# IMX8_DISPLAY.net
KiCad netlist of a schematic drawn in Altium Designer
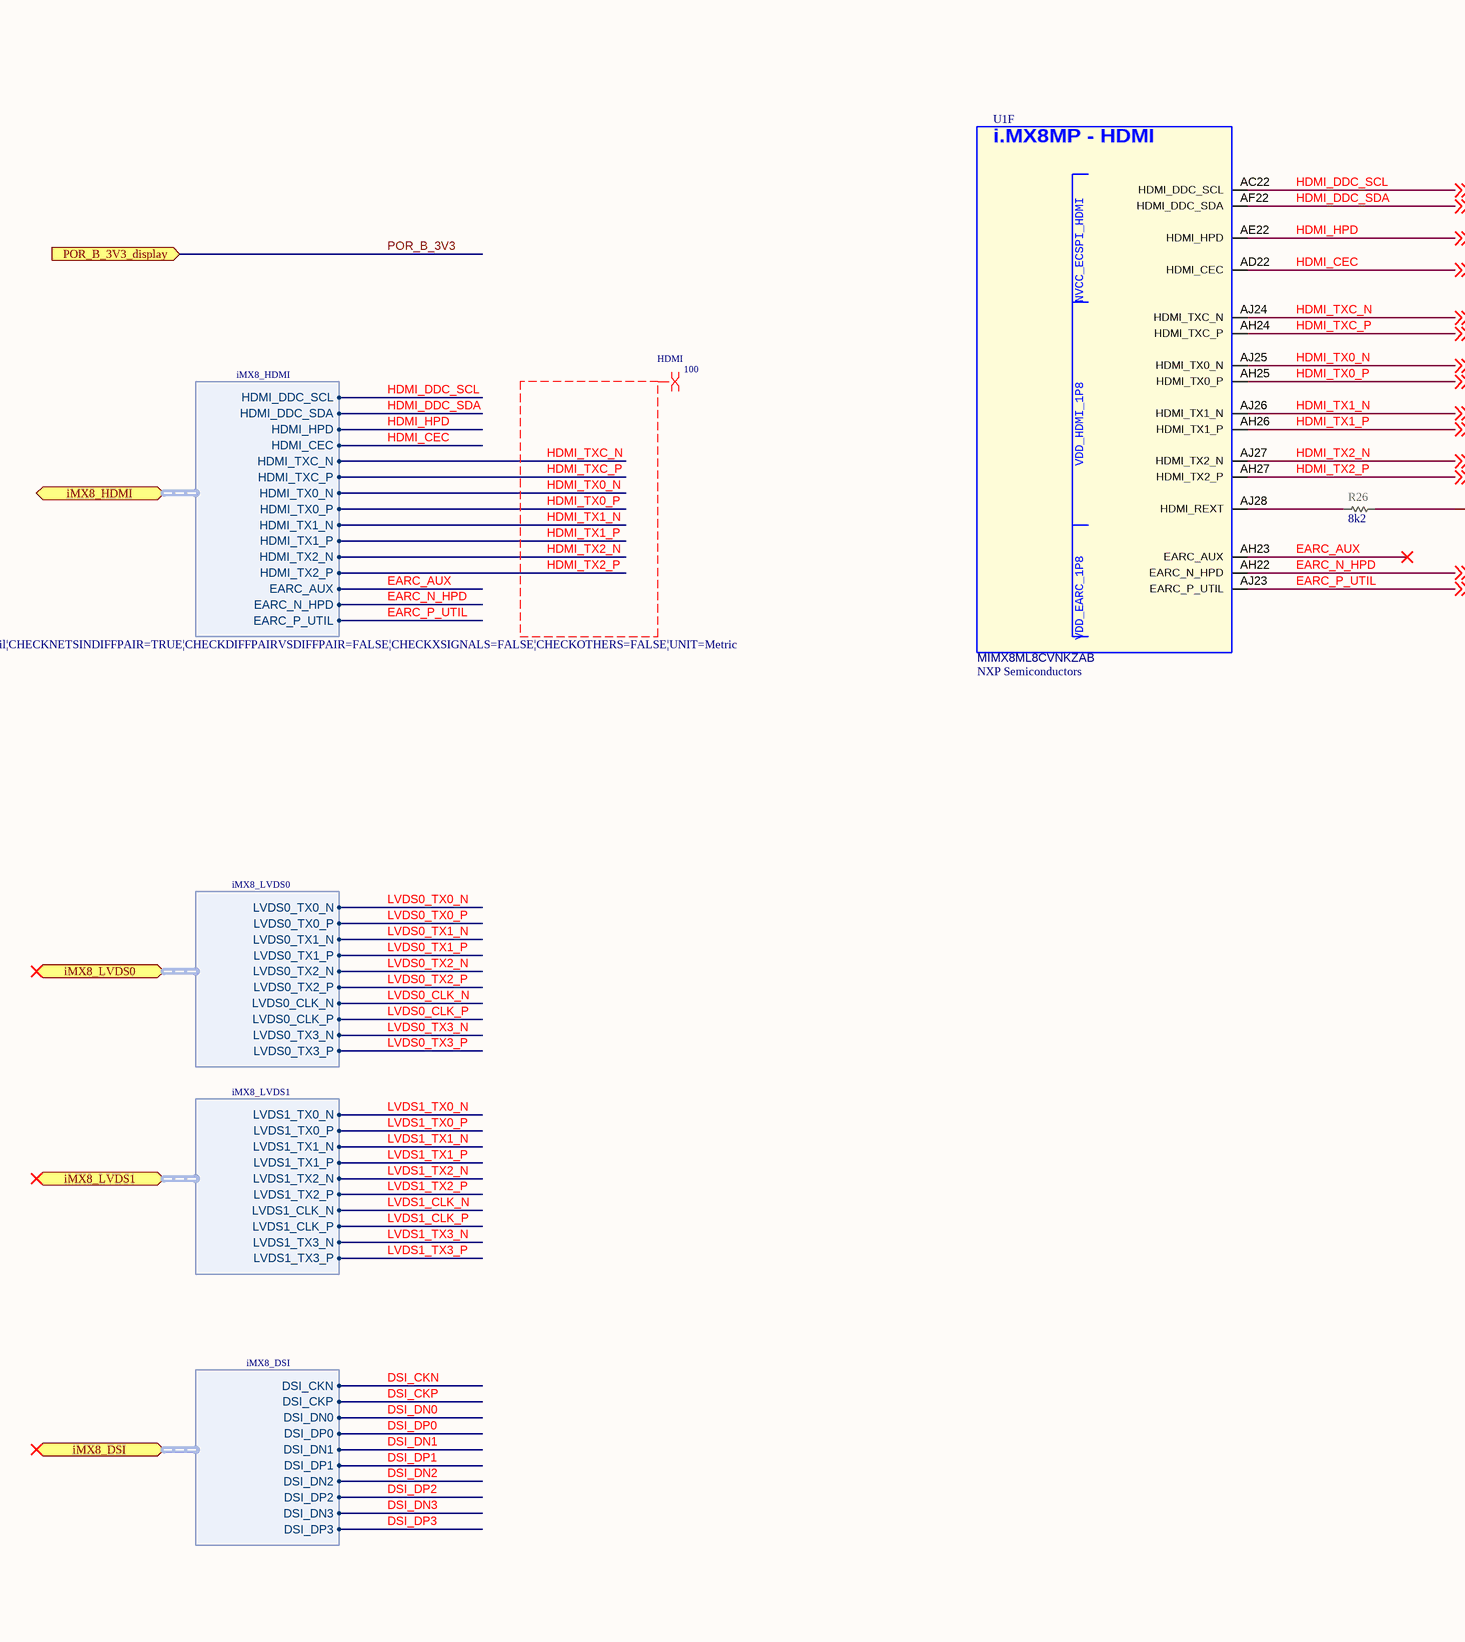
[diagram p0: IMX8_DISPLAY.SchDoc, left]
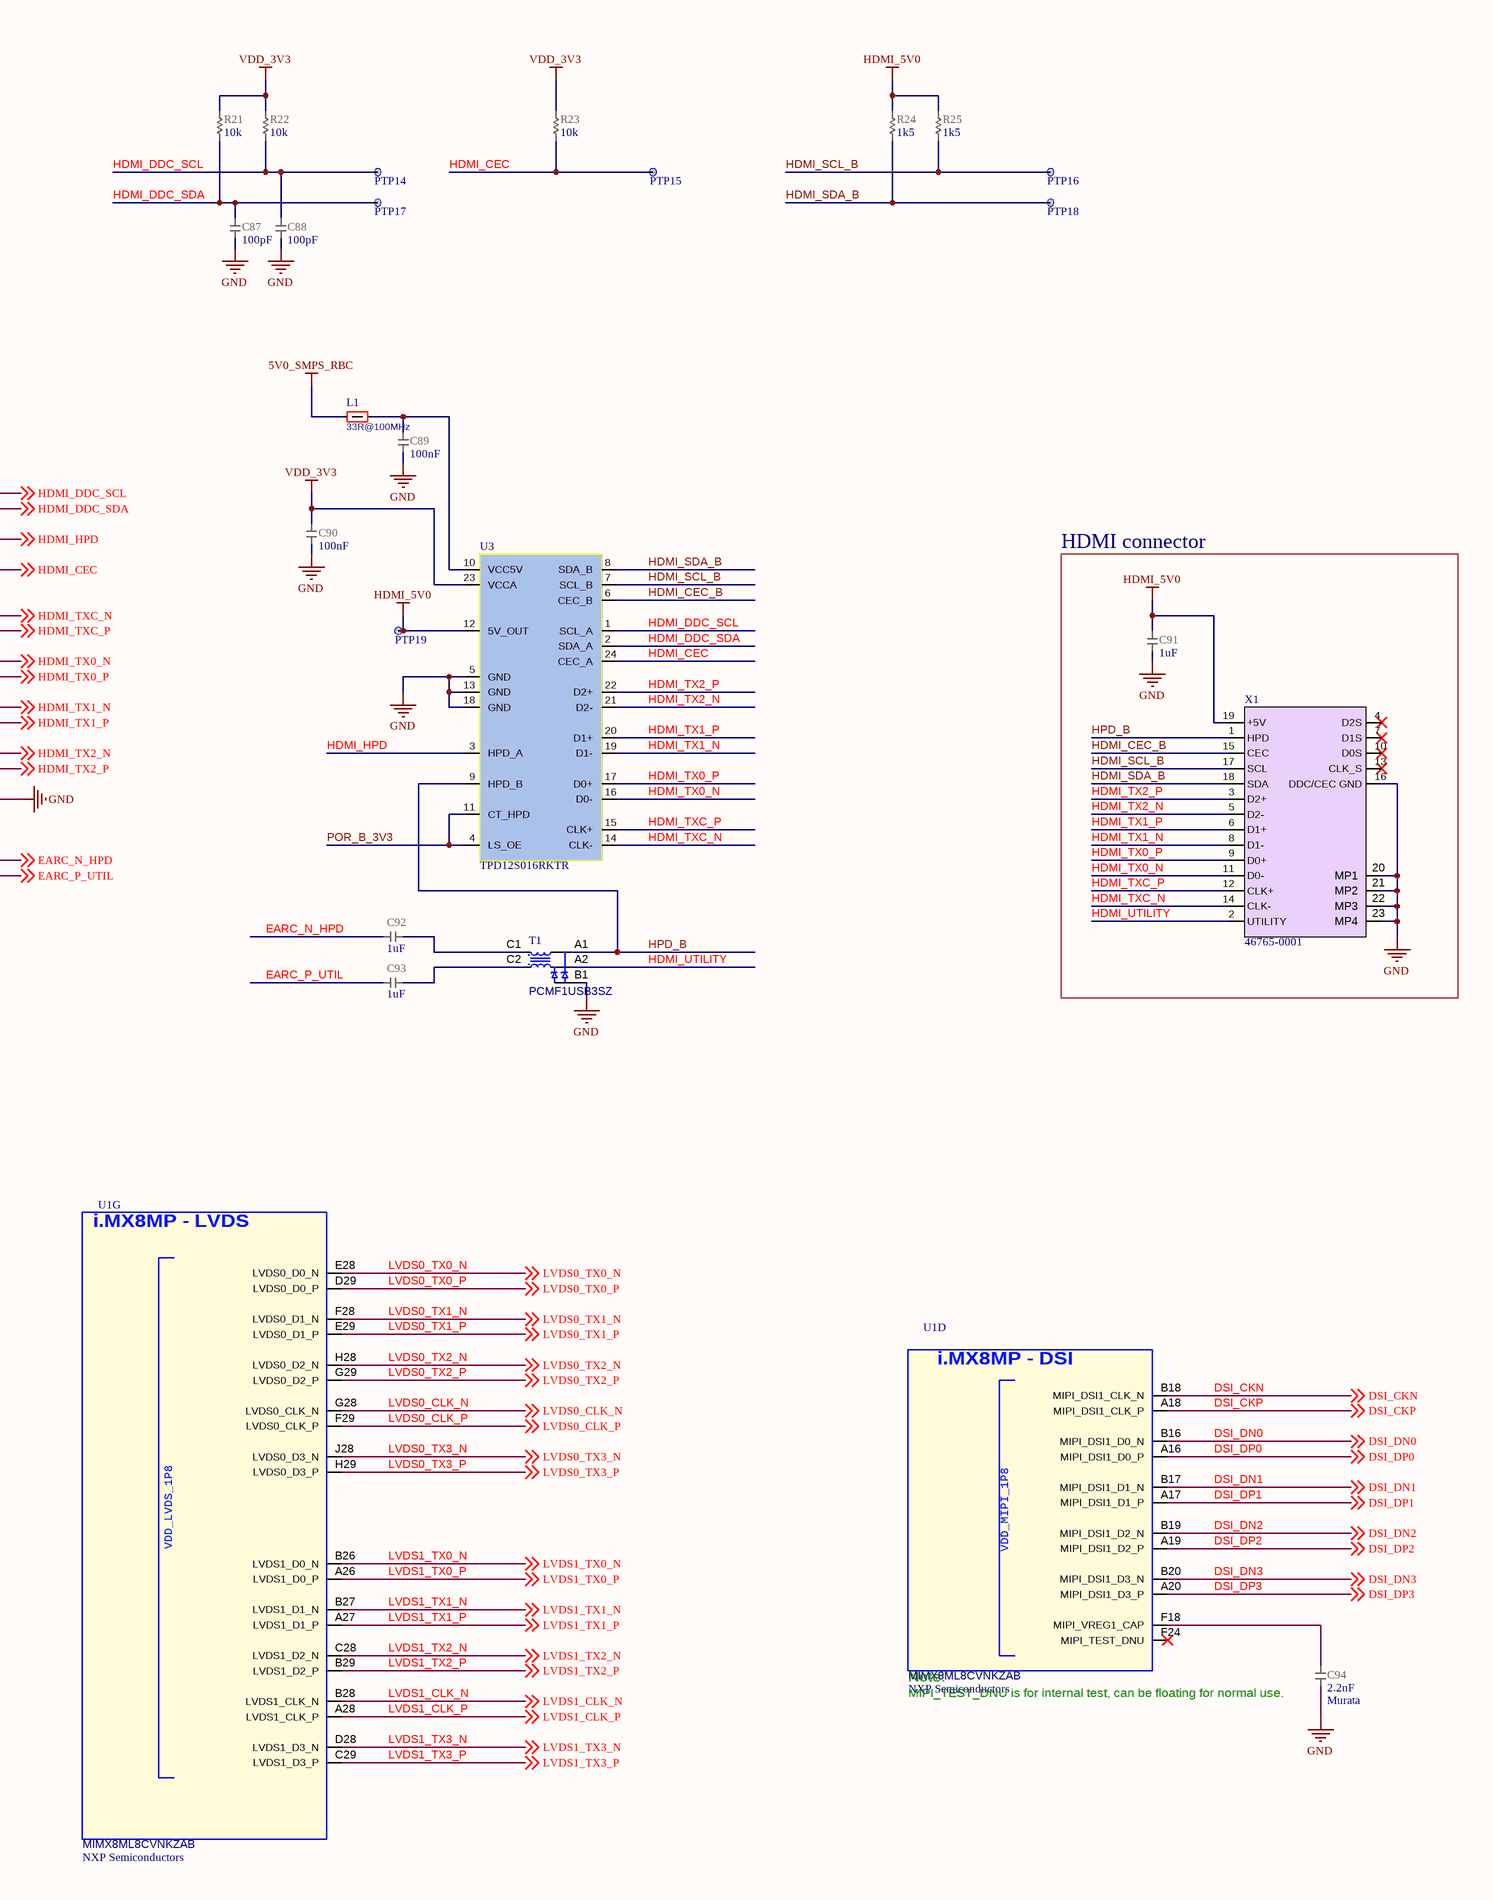
[diagram p1: IMX8_DISPLAY.SchDoc, right]

(export (version "E")
  (design (tool "Eeschema 10.0.6"))
  (components
    (comp (ref "C87")
      (value "100pF")
      (footprint "CAP_0201_UN1Q")
      (description "CAP")
      (fields (field (name "PART NUMBER") "CC0201KRX7R8BB101") (field (name "MANUFACTURER") "YAGEO"))
      (libsource (lib "TII_WS") (part "CAP_Common"))
    )
    (comp (ref "C88")
      (value "100pF")
      (footprint "CAP_0201_UN1Q")
      (description "CAP")
      (fields (field (name "PART NUMBER") "CC0201KRX7R8BB101") (field (name "MANUFACTURER") "YAGEO"))
      (libsource (lib "TII_WS") (part "CAP_Common"))
    )
    (comp (ref "C89")
      (value "100nF")
      (footprint "CAP_0201_UN1Q")
      (description "CAP")
      (fields (field (name "PART NUMBER") "GRM033C71C104KE14D") (field (name "MANUFACTURER") "Murata"))
      (libsource (lib "robo_cam") (part "CMP-001-000385-16"))
    )
    (comp (ref "C90")
      (value "100nF")
      (footprint "CAP_0201_UN1Q")
      (description "CAP")
      (fields (field (name "PART NUMBER") "GRM033C71C104KE14D") (field (name "MANUFACTURER") "Murata"))
      (libsource (lib "robo_cam") (part "CMP-001-000385-16"))
    )
    (comp (ref "C91")
      (value "1uF")
      (footprint "CAP_0201_UN1Q")
      (description "CAP")
      (fields (field (name "PART NUMBER") "KGM03CS61A105MH") (field (name "MANUFACTURER") "Kyocera"))
      (libsource (lib "robo_cam") (part "CMP-001-000336-15"))
    )
    (comp (ref "C92")
      (value "1uF")
      (footprint "CAP_0201_UN1Q")
      (description "CAP")
      (fields (field (name "PART NUMBER") "KGM03CS61A105MH") (field (name "MANUFACTURER") "Kyocera"))
      (libsource (lib "robo_cam") (part "CMP-001-000336-15"))
    )
    (comp (ref "C93")
      (value "1uF")
      (footprint "CAP_0201_UN1Q")
      (description "CAP")
      (fields (field (name "PART NUMBER") "KGM03CS61A105MH") (field (name "MANUFACTURER") "Kyocera"))
      (libsource (lib "robo_cam") (part "CMP-001-000336-15"))
    )
    (comp (ref "C94")
      (value "2.2nF")
      (footprint "CAP_0201_UN1Q")
      (description "CAP")
      (fields
        (field (name "PART NUMBER") "GRM033R71E222KA12J")
        (field (name "MANUFACTURER") "Murata")
        (field (name "MANUFACTURER_1") "Murata")
      )
      (libsource (lib "CM5_library") (part "CMP-001-000281-14"))
    )
    (comp (ref "L1")
      (value "33R@100MHz")
      (footprint "IND_0201_UN1Q")
      (description "FERRITE")
      (fields (field (name "MANUFACTURER") "Murata") (field (name "TOLERANCE") "25%"))
      (libsource (lib "robo_cam") (part "CMP-001-000744-7"))
    )
    (comp (ref "PTP14")
      (value "PTP_0.4mm")
      (footprint "PTP_0.4mm")
      (description "Production Testpoint 0.4mm. Flying probe. Use 1mm pitch.")
      (fields (field (name "PART NUMBER") "PTP 0.4mm"))
      (libsource (lib "robo_cam") (part "CMP-001-001296-3"))
    )
    (comp (ref "PTP15")
      (value "PTP_0.4mm")
      (footprint "PTP_0.4mm")
      (description "Production Testpoint 0.4mm. Flying probe. Use 1mm pitch.")
      (fields (field (name "PART NUMBER") "PTP 0.4mm"))
      (libsource (lib "robo_cam") (part "CMP-001-001296-3"))
    )
    (comp (ref "PTP16")
      (value "PTP_0.4mm")
      (footprint "PTP_0.4mm")
      (description "Production Testpoint 0.4mm. Flying probe. Use 1mm pitch.")
      (fields (field (name "PART NUMBER") "PTP 0.4mm"))
      (libsource (lib "robo_cam") (part "CMP-001-001296-3"))
    )
    (comp (ref "PTP17")
      (value "PTP_0.4mm")
      (footprint "PTP_0.4mm")
      (description "Production Testpoint 0.4mm. Flying probe. Use 1mm pitch.")
      (fields (field (name "PART NUMBER") "PTP 0.4mm"))
      (libsource (lib "robo_cam") (part "CMP-001-001296-3"))
    )
    (comp (ref "PTP18")
      (value "PTP_0.4mm")
      (footprint "PTP_0.4mm")
      (description "Production Testpoint 0.4mm. Flying probe. Use 1mm pitch.")
      (fields (field (name "PART NUMBER") "PTP 0.4mm"))
      (libsource (lib "robo_cam") (part "CMP-001-001296-3"))
    )
    (comp (ref "PTP19")
      (value "PTP_0.4mm")
      (footprint "PTP_0.4mm")
      (description "Production Testpoint 0.4mm. Flying probe. Use 1mm pitch.")
      (fields (field (name "PART NUMBER") "PTP 0.4mm"))
      (libsource (lib "robo_cam") (part "CMP-001-001296-3"))
    )
    (comp (ref "R21")
      (value "10k")
      (footprint "RES_0201_UN1Q")
      (description "RES")
      (fields (field (name "PART NUMBER") "RC0201FR-0710KL") (field (name "MANUFACTURER") "YAGEO"))
      (libsource (lib "robo_cam") (part "CMP-001-000446-13"))
    )
    (comp (ref "R22")
      (value "10k")
      (footprint "RES_0201_UN1Q")
      (description "RES")
      (fields (field (name "PART NUMBER") "RC0201FR-0710KL") (field (name "MANUFACTURER") "YAGEO"))
      (libsource (lib "robo_cam") (part "CMP-001-000446-13"))
    )
    (comp (ref "R23")
      (value "10k")
      (footprint "RES_0201_UN1Q")
      (description "RES")
      (fields (field (name "PART NUMBER") "RC0201FR-0710KL") (field (name "MANUFACTURER") "YAGEO"))
      (libsource (lib "robo_cam") (part "CMP-001-000446-13"))
    )
    (comp (ref "R24")
      (value "1k5")
      (footprint "RES_0201_UN1Q")
      (description "RES")
      (fields (field (name "PART NUMBER") "RC0201FR-071K5L") (field (name "MANUFACTURER") "YAGEO"))
      (libsource (lib "robo_cam") (part "CMP-001-000455-11"))
    )
    (comp (ref "R25")
      (value "1k5")
      (footprint "RES_0201_UN1Q")
      (description "RES")
      (fields (field (name "PART NUMBER") "RC0201FR-071K5L") (field (name "MANUFACTURER") "YAGEO"))
      (libsource (lib "robo_cam") (part "CMP-001-000455-11"))
    )
    (comp (ref "R26")
      (value "8k2")
      (footprint "RES_0201_UN1Q")
      (description "RES")
      (fields (field (name "TOLERANCE") "1%") (field (name "PART NUMBER") "ERJ1GNF8201C"))
      (libsource (lib "robo_cam") (part "CMP-001-001255-9"))
    )
    (comp (ref "T1")
      (value "EMI_ESD_PCMF1USB3SZ")
      (footprint "PCMF1USB3S_EMI")
      (description "EMI Filter with ESD 15kV differential pair")
      (fields
        (field (name "MANUFACTURER") "Nexperia")
        (field (name "PART NUMBER") "PCMF1USB3SZ")
        (field (name "MANUFACTURER PART NUMBER") "PCMF1USB3SZ")
        (field (name "SOURCE") "UUDET_KOMPONENTIT.SchLib")
      )
      (libsource (lib "robo_cam") (part "CMP-001-000967-4"))
    )
    (comp (ref "U1")
      (value "MIMX8ML8CVNKZAB")
      (footprint "BGA548C50P29X29_1500X1500X148")
      (description "CPU QUAD CORTEX A53+M4 1.6GHZ BGA548 Industrial")
      (fields
        (field (name "MANUFACTURER") "NXP SEMICONDUCTORS")
        (field (name "PART NUMBER") "MIMX8ML8CVNKZAB")
        (field (name "MANUFACTURER_1") "NXP Semiconductors")
        (field (name "SOURCE") "UUDET_KOMPONENTIT.SchLib")
      )
      (libsource (lib "robo_cam") (part "CMP-001-000983-8"))
    )
    (comp (ref "U3")
      (value "TPD12S016RKT")
      (footprint "UQFN24_RKT0024A_TI")
      (description "HDMI ESD Protection and I2C Level Shifting Buffer")
      (fields
        (field (name "MANUFACTURER") "Texas Instruments")
        (field (name "PART NUMBER") "TPD12S016RKTR")
        (field (name "MANUFACTURER PART NUMBER") "TPD12S016RKTR")
        (field (name "SOURCE") "UUDET_KOMPONENTIT.SchLib")
      )
      (libsource (lib "robo_cam") (part "CMP-031-000038-2"))
    )
    (comp (ref "X1")
      (value "Molex_uHDMI_46765-0001")
      (footprint "uHDMI-SMD-Molex")
      (description "Micro-HDMI connector, surface mount")
      (fields
        (field (name "MANUFACTURER") "Molex")
        (field (name "PART NUMBER") "46765-0001")
        (field (name "MANUFACTURER PART NUMBER") "46765-0001")
      )
      (libsource (lib "robo_cam") (part "CMP-001-000218-15"))
    )
  )
  (nets
    (net (code "5") (name "/EARC_AUX") (class "Default")
      (node (ref "U1") (pin "AH23") (pinfunction "EARC_AUX_AH23") (pintype "passive+no_connect"))
    )
    (net (code "6") (name "/HDMI_CEC_B") (class "Default")
      (node (ref "U3") (pin "6") (pinfunction "CEC_B_6") (pintype "passive"))
      (node (ref "X1") (pin "15") (pinfunction "CEC_15") (pintype "passive"))
    )
    (net (code "7") (name "/HDMI_SCL_B") (class "Default")
      (node (ref "PTP16") (pin "1") (pinfunction "TP_1") (pintype "passive"))
      (node (ref "R25") (pin "1") (pinfunction "1_1") (pintype "passive"))
      (node (ref "U3") (pin "7") (pinfunction "SCL_B_7") (pintype "passive"))
      (node (ref "X1") (pin "17") (pinfunction "SCL_17") (pintype "passive"))
    )
    (net (code "8") (name "/HDMI_SDA_B") (class "Default")
      (node (ref "PTP18") (pin "1") (pinfunction "TP_1") (pintype "passive"))
      (node (ref "R24") (pin "1") (pinfunction "1_1") (pintype "passive"))
      (node (ref "U3") (pin "8") (pinfunction "SDA_B_8") (pintype "passive"))
      (node (ref "X1") (pin "18") (pinfunction "SDA_18") (pintype "passive"))
    )
    (net (code "9") (name "/HDMI_UTILITY") (class "Default")
      (node (ref "T1") (pin "A2") (pinfunction "A2_A2") (pintype "passive"))
      (node (ref "X1") (pin "2") (pinfunction "UTILITY_2") (pintype "passive"))
    )
    (net (code "10") (name "/HPD_B") (class "Default")
      (node (ref "T1") (pin "A1") (pinfunction "A1_A1") (pintype "passive"))
      (node (ref "U3") (pin "9") (pinfunction "HPD_B_9") (pintype "passive"))
      (node (ref "X1") (pin "1") (pinfunction "HPD_1") (pintype "passive"))
    )
    (net (code "11") (name "/POR_B_3V3") (class "Default")
      (node (ref "U3") (pin "11") (pinfunction "CT_HPD_11") (pintype "passive"))
      (node (ref "U3") (pin "4") (pinfunction "LS_OE_4") (pintype "passive"))
    )
    (net (code "16") (name "5V0_SMPS_RBC") (class "Default")
      (node (ref "L1") (pin "1") (pinfunction "1_1") (pintype "passive"))
    )
    (net (code "17") (name "DSI_CKN") (class "Default")
      (node (ref "U1") (pin "B18") (pinfunction "MIPI_DSI1_CLK_N_B18") (pintype "passive"))
    )
    (net (code "18") (name "DSI_CKP") (class "Default")
      (node (ref "U1") (pin "A18") (pinfunction "MIPI_DSI1_CLK_P_A18") (pintype "passive"))
    )
    (net (code "19") (name "DSI_DN0") (class "Default")
      (node (ref "U1") (pin "B16") (pinfunction "MIPI_DSI1_D0_N_B16") (pintype "passive"))
    )
    (net (code "20") (name "DSI_DN1") (class "Default")
      (node (ref "U1") (pin "B17") (pinfunction "MIPI_DSI1_D1_N_B17") (pintype "passive"))
    )
    (net (code "21") (name "DSI_DN2") (class "Default")
      (node (ref "U1") (pin "B19") (pinfunction "MIPI_DSI1_D2_N_B19") (pintype "passive"))
    )
    (net (code "22") (name "DSI_DN3") (class "Default")
      (node (ref "U1") (pin "B20") (pinfunction "MIPI_DSI1_D3_N_B20") (pintype "passive"))
    )
    (net (code "23") (name "DSI_DP0") (class "Default")
      (node (ref "U1") (pin "A16") (pinfunction "MIPI_DSI1_D0_P_A16") (pintype "passive"))
    )
    (net (code "24") (name "DSI_DP1") (class "Default")
      (node (ref "U1") (pin "A17") (pinfunction "MIPI_DSI1_D1_P_A17") (pintype "passive"))
    )
    (net (code "25") (name "DSI_DP2") (class "Default")
      (node (ref "U1") (pin "A19") (pinfunction "MIPI_DSI1_D2_P_A19") (pintype "passive"))
    )
    (net (code "26") (name "DSI_DP3") (class "Default")
      (node (ref "U1") (pin "A20") (pinfunction "MIPI_DSI1_D3_P_A20") (pintype "passive"))
    )
    (net (code "27") (name "EARC_N_HPD") (class "Default")
      (node (ref "C92") (pin "1") (pinfunction "1_1") (pintype "passive"))
      (node (ref "U1") (pin "AH22") (pinfunction "EARC_N_HPD_AH22") (pintype "passive"))
    )
    (net (code "28") (name "EARC_P_UTIL") (class "Default")
      (node (ref "C93") (pin "1") (pinfunction "1_1") (pintype "passive"))
      (node (ref "U1") (pin "AJ23") (pinfunction "EARC_P_UTIL_AJ23") (pintype "passive"))
    )
    (net (code "29") (name "GND") (class "Default")
      (node (ref "C87") (pin "1") (pinfunction "1_1") (pintype "passive"))
      (node (ref "C88") (pin "1") (pinfunction "1_1") (pintype "passive"))
      (node (ref "C89") (pin "2") (pinfunction "2_2") (pintype "passive"))
      (node (ref "C90") (pin "2") (pinfunction "2_2") (pintype "passive"))
      (node (ref "C91") (pin "1") (pinfunction "1_1") (pintype "passive"))
      (node (ref "C94") (pin "1") (pinfunction "1_1") (pintype "passive"))
      (node (ref "R26") (pin "2") (pinfunction "2_2") (pintype "passive"))
      (node (ref "T1") (pin "B1") (pinfunction "B1_B1") (pintype "passive"))
      (node (ref "U3") (pin "13") (pinfunction "GND_13") (pintype "passive"))
      (node (ref "U3") (pin "18") (pinfunction "GND_18") (pintype "passive"))
      (node (ref "U3") (pin "5") (pinfunction "GND_5") (pintype "passive"))
      (node (ref "X1") (pin "16") (pinfunction "DDC/CEC_GND_16") (pintype "passive"))
      (node (ref "X1") (pin "20") (pinfunction "MP1_20") (pintype "passive"))
      (node (ref "X1") (pin "21") (pinfunction "MP2_21") (pintype "passive"))
      (node (ref "X1") (pin "22") (pinfunction "MP3_22") (pintype "passive"))
      (node (ref "X1") (pin "23") (pinfunction "MP4_23") (pintype "passive"))
    )
    (net (code "30") (name "HDMI_5V0") (class "Default")
      (node (ref "C91") (pin "2") (pinfunction "2_2") (pintype "passive"))
      (node (ref "PTP19") (pin "1") (pinfunction "TP_1") (pintype "passive"))
      (node (ref "R24") (pin "2") (pinfunction "2_2") (pintype "passive"))
      (node (ref "R25") (pin "2") (pinfunction "2_2") (pintype "passive"))
      (node (ref "U3") (pin "12") (pinfunction "5V_OUT_12") (pintype "passive"))
      (node (ref "X1") (pin "19") (pinfunction "+5V_19") (pintype "passive"))
    )
    (net (code "31") (name "HDMI_CEC") (class "Default")
      (node (ref "PTP15") (pin "1") (pinfunction "TP_1") (pintype "passive"))
      (node (ref "R23") (pin "1") (pinfunction "1_1") (pintype "passive"))
      (node (ref "U1") (pin "AD22") (pinfunction "HDMI_CEC_AD22") (pintype "passive"))
      (node (ref "U3") (pin "24") (pinfunction "CEC_A_24") (pintype "passive"))
    )
    (net (code "32") (name "HDMI_DDC_SCL") (class "Default")
      (node (ref "C88") (pin "2") (pinfunction "2_2") (pintype "passive"))
      (node (ref "PTP14") (pin "1") (pinfunction "TP_1") (pintype "passive"))
      (node (ref "R22") (pin "1") (pinfunction "1_1") (pintype "passive"))
      (node (ref "U1") (pin "AC22") (pinfunction "HDMI_DDC_SCL_AC22") (pintype "passive"))
      (node (ref "U3") (pin "1") (pinfunction "SCL_A_1") (pintype "passive"))
    )
    (net (code "33") (name "HDMI_DDC_SDA") (class "Default")
      (node (ref "C87") (pin "2") (pinfunction "2_2") (pintype "passive"))
      (node (ref "PTP17") (pin "1") (pinfunction "TP_1") (pintype "passive"))
      (node (ref "R21") (pin "1") (pinfunction "1_1") (pintype "passive"))
      (node (ref "U1") (pin "AF22") (pinfunction "HDMI_DDC_SDA_AF22") (pintype "passive"))
      (node (ref "U3") (pin "2") (pinfunction "SDA_A_2") (pintype "passive"))
    )
    (net (code "34") (name "HDMI_HPD") (class "Default")
      (node (ref "U1") (pin "AE22") (pinfunction "HDMI_HPD_AE22") (pintype "passive"))
      (node (ref "U3") (pin "3") (pinfunction "HPD_A_3") (pintype "passive"))
    )
    (net (code "35") (name "HDMI_TX0_N") (class "Default")
      (node (ref "U1") (pin "AJ25") (pinfunction "HDMI_TX0_N_AJ25") (pintype "passive"))
      (node (ref "U3") (pin "16") (pinfunction "D0-_16") (pintype "passive"))
      (node (ref "X1") (pin "11") (pinfunction "D0-_11") (pintype "passive"))
    )
    (net (code "36") (name "HDMI_TX0_P") (class "Default")
      (node (ref "U1") (pin "AH25") (pinfunction "HDMI_TX0_P_AH25") (pintype "passive"))
      (node (ref "U3") (pin "17") (pinfunction "D0+_17") (pintype "passive"))
      (node (ref "X1") (pin "9") (pinfunction "D0+_9") (pintype "passive"))
    )
    (net (code "37") (name "HDMI_TX1_N") (class "Default")
      (node (ref "U1") (pin "AJ26") (pinfunction "HDMI_TX1_N_AJ26") (pintype "passive"))
      (node (ref "U3") (pin "19") (pinfunction "D1-_19") (pintype "passive"))
      (node (ref "X1") (pin "8") (pinfunction "D1-_8") (pintype "passive"))
    )
    (net (code "38") (name "HDMI_TX1_P") (class "Default")
      (node (ref "U1") (pin "AH26") (pinfunction "HDMI_TX1_P_AH26") (pintype "passive"))
      (node (ref "U3") (pin "20") (pinfunction "D1+_20") (pintype "passive"))
      (node (ref "X1") (pin "6") (pinfunction "D1+_6") (pintype "passive"))
    )
    (net (code "39") (name "HDMI_TX2_N") (class "Default")
      (node (ref "U1") (pin "AJ27") (pinfunction "HDMI_TX2_N_AJ27") (pintype "passive"))
      (node (ref "U3") (pin "21") (pinfunction "D2-_21") (pintype "passive"))
      (node (ref "X1") (pin "5") (pinfunction "D2-_5") (pintype "passive"))
    )
    (net (code "40") (name "HDMI_TX2_P") (class "Default")
      (node (ref "U1") (pin "AH27") (pinfunction "HDMI_TX2_P_AH27") (pintype "passive"))
      (node (ref "U3") (pin "22") (pinfunction "D2+_22") (pintype "passive"))
      (node (ref "X1") (pin "3") (pinfunction "D2+_3") (pintype "passive"))
    )
    (net (code "41") (name "HDMI_TXC_N") (class "Default")
      (node (ref "U1") (pin "AJ24") (pinfunction "HDMI_TXC_N_AJ24") (pintype "passive"))
      (node (ref "U3") (pin "14") (pinfunction "CLK-_14") (pintype "passive"))
      (node (ref "X1") (pin "14") (pinfunction "CLK-_14") (pintype "passive"))
    )
    (net (code "42") (name "HDMI_TXC_P") (class "Default")
      (node (ref "U1") (pin "AH24") (pinfunction "HDMI_TXC_P_AH24") (pintype "passive"))
      (node (ref "U3") (pin "15") (pinfunction "CLK+_15") (pintype "passive"))
      (node (ref "X1") (pin "12") (pinfunction "CLK+_12") (pintype "passive"))
    )
    (net (code "43") (name "LVDS0_CLK_N") (class "Default")
      (node (ref "U1") (pin "G28") (pinfunction "LVDS0_CLK_N_G28") (pintype "passive"))
    )
    (net (code "44") (name "LVDS0_CLK_P") (class "Default")
      (node (ref "U1") (pin "F29") (pinfunction "LVDS0_CLK_P_F29") (pintype "passive"))
    )
    (net (code "45") (name "LVDS0_TX0_N") (class "Default")
      (node (ref "U1") (pin "E28") (pinfunction "LVDS0_D0_N_E28") (pintype "passive"))
    )
    (net (code "46") (name "LVDS0_TX0_P") (class "Default")
      (node (ref "U1") (pin "D29") (pinfunction "LVDS0_D0_P_D29") (pintype "passive"))
    )
    (net (code "47") (name "LVDS0_TX1_N") (class "Default")
      (node (ref "U1") (pin "F28") (pinfunction "LVDS0_D1_N_F28") (pintype "passive"))
    )
    (net (code "48") (name "LVDS0_TX1_P") (class "Default")
      (node (ref "U1") (pin "E29") (pinfunction "LVDS0_D1_P_E29") (pintype "passive"))
    )
    (net (code "49") (name "LVDS0_TX2_N") (class "Default")
      (node (ref "U1") (pin "H28") (pinfunction "LVDS0_D2_N_H28") (pintype "passive"))
    )
    (net (code "50") (name "LVDS0_TX2_P") (class "Default")
      (node (ref "U1") (pin "G29") (pinfunction "LVDS0_D2_P_G29") (pintype "passive"))
    )
    (net (code "51") (name "LVDS0_TX3_N") (class "Default")
      (node (ref "U1") (pin "J28") (pinfunction "LVDS0_D3_N_J28") (pintype "passive"))
    )
    (net (code "52") (name "LVDS0_TX3_P") (class "Default")
      (node (ref "U1") (pin "H29") (pinfunction "LVDS0_D3_P_H29") (pintype "passive"))
    )
    (net (code "53") (name "LVDS1_CLK_N") (class "Default")
      (node (ref "U1") (pin "B28") (pinfunction "LVDS1_CLK_N_B28") (pintype "passive"))
    )
    (net (code "54") (name "LVDS1_CLK_P") (class "Default")
      (node (ref "U1") (pin "A28") (pinfunction "LVDS1_CLK_P_A28") (pintype "passive"))
    )
    (net (code "55") (name "LVDS1_TX0_N") (class "Default")
      (node (ref "U1") (pin "B26") (pinfunction "LVDS1_D0_N_B26") (pintype "passive"))
    )
    (net (code "56") (name "LVDS1_TX0_P") (class "Default")
      (node (ref "U1") (pin "A26") (pinfunction "LVDS1_D0_P_A26") (pintype "passive"))
    )
    (net (code "57") (name "LVDS1_TX1_N") (class "Default")
      (node (ref "U1") (pin "B27") (pinfunction "LVDS1_D1_N_B27") (pintype "passive"))
    )
    (net (code "58") (name "LVDS1_TX1_P") (class "Default")
      (node (ref "U1") (pin "A27") (pinfunction "LVDS1_D1_P_A27") (pintype "passive"))
    )
    (net (code "59") (name "LVDS1_TX2_N") (class "Default")
      (node (ref "U1") (pin "C28") (pinfunction "LVDS1_D2_N_C28") (pintype "passive"))
    )
    (net (code "60") (name "LVDS1_TX2_P") (class "Default")
      (node (ref "U1") (pin "B29") (pinfunction "LVDS1_D2_P_B29") (pintype "passive"))
    )
    (net (code "61") (name "LVDS1_TX3_N") (class "Default")
      (node (ref "U1") (pin "D28") (pinfunction "LVDS1_D3_N_D28") (pintype "passive"))
    )
    (net (code "62") (name "LVDS1_TX3_P") (class "Default")
      (node (ref "U1") (pin "C29") (pinfunction "LVDS1_D3_P_C29") (pintype "passive"))
    )
    (net (code "63") (name "Net-(C92-Pad2)") (class "Default")
      (node (ref "C92") (pin "2") (pinfunction "2_2") (pintype "passive"))
      (node (ref "T1") (pin "C1") (pinfunction "C1_C1") (pintype "passive"))
    )
    (net (code "64") (name "Net-(C93-Pad2)") (class "Default")
      (node (ref "C93") (pin "2") (pinfunction "2_2") (pintype "passive"))
      (node (ref "T1") (pin "C2") (pinfunction "C2_C2") (pintype "passive"))
    )
    (net (code "65") (name "Net-(U1D-MIPI_VREG1_CAP)") (class "Default")
      (node (ref "C94") (pin "2") (pinfunction "2_2") (pintype "passive"))
      (node (ref "U1") (pin "F18") (pinfunction "MIPI_VREG1_CAP_F18") (pintype "passive"))
    )
    (net (code "66") (name "Net-(U1F-HDMI_REXT)") (class "Default")
      (node (ref "R26") (pin "1") (pinfunction "1_1") (pintype "passive"))
      (node (ref "U1") (pin "AJ28") (pinfunction "HDMI_REXT_AJ28") (pintype "passive"))
    )
    (net (code "67") (name "Net-(U3-VCC5V)") (class "Default")
      (node (ref "C89") (pin "1") (pinfunction "1_1") (pintype "passive"))
      (node (ref "L1") (pin "2") (pinfunction "2_2") (pintype "passive"))
      (node (ref "U3") (pin "10") (pinfunction "VCC5V_10") (pintype "passive"))
    )
    (net (code "68") (name "VDD_3V3") (class "Default")
      (node (ref "C90") (pin "1") (pinfunction "1_1") (pintype "passive"))
      (node (ref "R21") (pin "2") (pinfunction "2_2") (pintype "passive"))
      (node (ref "R22") (pin "2") (pinfunction "2_2") (pintype "passive"))
      (node (ref "R23") (pin "2") (pinfunction "2_2") (pintype "passive"))
      (node (ref "U3") (pin "23") (pinfunction "VCCA_23") (pintype "passive"))
    )
    (net (code "69") (name "unconnected-(U1D-MIPI_TEST_DNU-PadF24)") (class "Default")
      (node (ref "U1") (pin "F24") (pinfunction "MIPI_TEST_DNU_F24") (pintype "passive+no_connect"))
    )
    (net (code "70") (name "unconnected-(X1-CLK_S-Pad13)") (class "Default")
      (node (ref "X1") (pin "13") (pinfunction "CLK_S_13") (pintype "passive+no_connect"))
    )
    (net (code "71") (name "unconnected-(X1-D0S-Pad10)") (class "Default")
      (node (ref "X1") (pin "10") (pinfunction "D0S_10") (pintype "passive+no_connect"))
    )
    (net (code "72") (name "unconnected-(X1-D1S-Pad7)") (class "Default")
      (node (ref "X1") (pin "7") (pinfunction "D1S_7") (pintype "passive+no_connect"))
    )
    (net (code "73") (name "unconnected-(X1-D2S-Pad4)") (class "Default")
      (node (ref "X1") (pin "4") (pinfunction "D2S_4") (pintype "passive+no_connect"))
    )
  )
)
